# 5v-to220.net
KiCad netlist of a schematic drawn in EAGLE
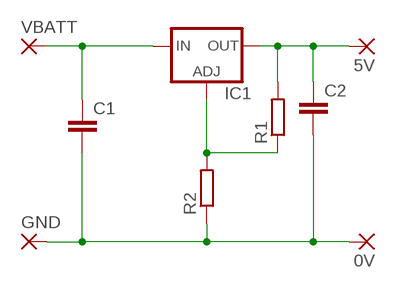
[diagram p0: schematic, sheet 1]

(export (version "E")
  (design (tool "Eeschema 10.0.6"))
  (components
    (comp (ref "0V")
      (value "WIREPAD4,16O1,6")
      (footprint "eagle-import:4,16O1,6")
      (libsource (lib "eagle-import") (part "WIREPAD4,16O1,6"))
    )
    (comp (ref "5V")
      (value "WIREPAD4,16O1,6")
      (footprint "eagle-import:4,16O1,6")
      (libsource (lib "eagle-import") (part "WIREPAD4,16O1,6"))
    )
    (comp (ref "C1")
      (value "C-EU050-024X044")
      (footprint "eagle-import:C050-024X044")
      (libsource (lib "eagle-import") (part "C-EU050-024X044"))
    )
    (comp (ref "C2")
      (value "C-EU050-024X044")
      (footprint "eagle-import:C050-024X044")
      (libsource (lib "eagle-import") (part "C-EU050-024X044"))
    )
    (comp (ref "GND")
      (value "WIREPAD4,16O1,6")
      (footprint "eagle-import:4,16O1,6")
      (libsource (lib "eagle-import") (part "WIREPAD4,16O1,6"))
    )
    (comp (ref "IC1")
      (value "LM138-TL")
      (footprint "eagle-import:TO220L1")
      (libsource (lib "eagle-import") (part "LM138-TL"))
    )
    (comp (ref "R1")
      (value "R-EU_0207/10")
      (footprint "eagle-import:0207_10")
      (libsource (lib "eagle-import") (part "R-EU_0207/10"))
    )
    (comp (ref "R2")
      (value "R-EU_0207/10")
      (footprint "eagle-import:0207_10")
      (libsource (lib "eagle-import") (part "R-EU_0207/10"))
    )
    (comp (ref "VBATT")
      (value "WIREPAD4,16O1,6")
      (footprint "eagle-import:4,16O1,6")
      (libsource (lib "eagle-import") (part "WIREPAD4,16O1,6"))
    )
  )
  (nets
    (net (code "1") (name "Net-(0V-P)") (class "Default")
      (node (ref "0V") (pin "1") (pinfunction "P_1") (pintype "passive"))
      (node (ref "C1") (pin "2") (pinfunction "2_2") (pintype "passive"))
      (node (ref "C2") (pin "2") (pinfunction "2_2") (pintype "passive"))
      (node (ref "GND") (pin "1") (pinfunction "P_1") (pintype "passive"))
      (node (ref "R2") (pin "1") (pinfunction "1_1") (pintype "passive"))
    )
    (net (code "2") (name "Net-(5V-P)") (class "Default")
      (node (ref "5V") (pin "1") (pinfunction "P_1") (pintype "passive"))
      (node (ref "C2") (pin "1") (pinfunction "1_1") (pintype "passive"))
      (node (ref "IC1") (pin "2") (pinfunction "OUT_2") (pintype "passive"))
      (node (ref "R1") (pin "2") (pinfunction "2_2") (pintype "passive"))
    )
    (net (code "3") (name "Net-(IC1-ADJ)") (class "Default")
      (node (ref "IC1") (pin "1") (pinfunction "ADJ_1") (pintype "input"))
      (node (ref "R1") (pin "1") (pinfunction "1_1") (pintype "passive"))
      (node (ref "R2") (pin "2") (pinfunction "2_2") (pintype "passive"))
    )
    (net (code "4") (name "Net-(IC1-IN)") (class "Default")
      (node (ref "C1") (pin "1") (pinfunction "1_1") (pintype "passive"))
      (node (ref "IC1") (pin "3") (pinfunction "IN_3") (pintype "input"))
      (node (ref "VBATT") (pin "1") (pinfunction "P_1") (pintype "passive"))
    )
  )
)
